# buff_statue.net
KiCad netlist of a schematic drawn in EAGLE
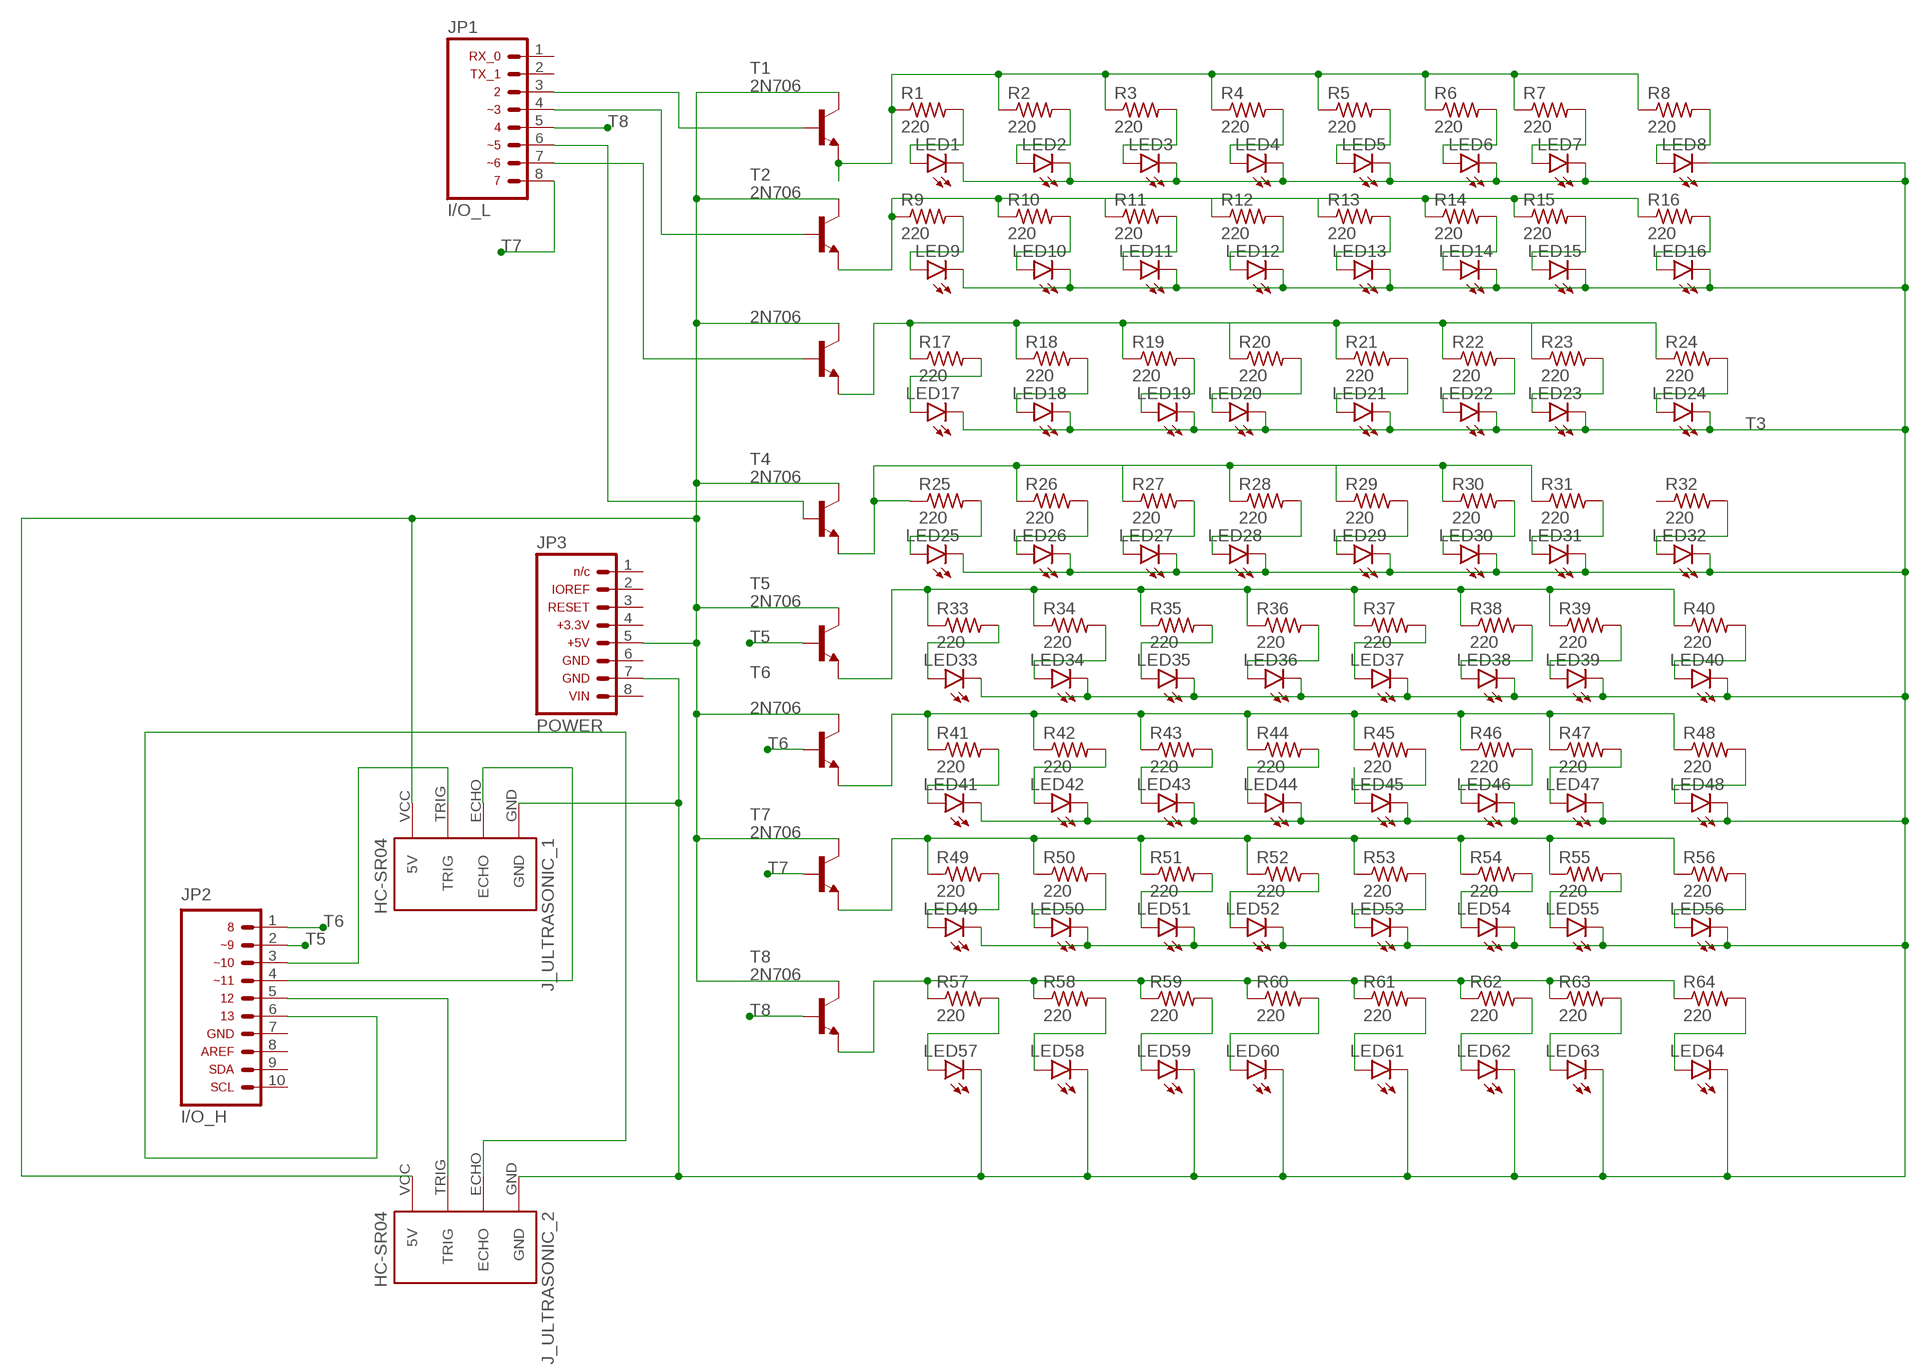
[diagram p0: schematic, sheet 1]

(export (version "E")
  (design (tool "Eeschema 10.0.6"))
  (components
    (comp (ref "JP1")
      (value "ARDUINO_CONN-IO_LSIP")
      (footprint "eagle-import:CONN-1X08")
      (libsource (lib "eagle-import") (part "ARDUINO_CONN-IO_LSIP"))
    )
    (comp (ref "JP2")
      (value "ARDUINO_CONN-IO_HSIP")
      (footprint "eagle-import:CONN-1X10")
      (libsource (lib "eagle-import") (part "ARDUINO_CONN-IO_HSIP"))
    )
    (comp (ref "JP3")
      (value "ARDUINO_CONN-POWERSIP")
      (footprint "eagle-import:CONN-1X08")
      (libsource (lib "eagle-import") (part "ARDUINO_CONN-POWERSIP"))
    )
    (comp (ref "J_ULTRASONIC_1")
      (value "HC-SR04")
      (footprint "eagle-import:HC-SR04_FOOTPRINT")
      (libsource (lib "eagle-import") (part "HC-SR04"))
    )
    (comp (ref "J_ULTRASONIC_2")
      (value "HC-SR04")
      (footprint "eagle-import:HC-SR04_FOOTPRINT")
      (libsource (lib "eagle-import") (part "HC-SR04"))
    )
    (comp (ref "LED1")
      (value "LED5MM")
      (footprint "eagle-import:LED5MM")
      (libsource (lib "eagle-import") (part "LED5MM"))
    )
    (comp (ref "LED2")
      (value "LED5MM")
      (footprint "eagle-import:LED5MM")
      (libsource (lib "eagle-import") (part "LED5MM"))
    )
    (comp (ref "LED3")
      (value "LED5MM")
      (footprint "eagle-import:LED5MM")
      (libsource (lib "eagle-import") (part "LED5MM"))
    )
    (comp (ref "LED4")
      (value "LED5MM")
      (footprint "eagle-import:LED5MM")
      (libsource (lib "eagle-import") (part "LED5MM"))
    )
    (comp (ref "LED5")
      (value "LED5MM")
      (footprint "eagle-import:LED5MM")
      (libsource (lib "eagle-import") (part "LED5MM"))
    )
    (comp (ref "LED6")
      (value "LED5MM")
      (footprint "eagle-import:LED5MM")
      (libsource (lib "eagle-import") (part "LED5MM"))
    )
    (comp (ref "LED7")
      (value "LED5MM")
      (footprint "eagle-import:LED5MM")
      (libsource (lib "eagle-import") (part "LED5MM"))
    )
    (comp (ref "LED8")
      (value "LED5MM")
      (footprint "eagle-import:LED5MM")
      (libsource (lib "eagle-import") (part "LED5MM"))
    )
    (comp (ref "LED9")
      (value "LED5MM")
      (footprint "eagle-import:LED5MM")
      (libsource (lib "eagle-import") (part "LED5MM"))
    )
    (comp (ref "LED10")
      (value "LED5MM")
      (footprint "eagle-import:LED5MM")
      (libsource (lib "eagle-import") (part "LED5MM"))
    )
    (comp (ref "LED11")
      (value "LED5MM")
      (footprint "eagle-import:LED5MM")
      (libsource (lib "eagle-import") (part "LED5MM"))
    )
    (comp (ref "LED12")
      (value "LED5MM")
      (footprint "eagle-import:LED5MM")
      (libsource (lib "eagle-import") (part "LED5MM"))
    )
    (comp (ref "LED13")
      (value "LED5MM")
      (footprint "eagle-import:LED5MM")
      (libsource (lib "eagle-import") (part "LED5MM"))
    )
    (comp (ref "LED14")
      (value "LED5MM")
      (footprint "eagle-import:LED5MM")
      (libsource (lib "eagle-import") (part "LED5MM"))
    )
    (comp (ref "LED15")
      (value "LED5MM")
      (footprint "eagle-import:LED5MM")
      (libsource (lib "eagle-import") (part "LED5MM"))
    )
    (comp (ref "LED16")
      (value "LED5MM")
      (footprint "eagle-import:LED5MM")
      (libsource (lib "eagle-import") (part "LED5MM"))
    )
    (comp (ref "LED17")
      (value "LED5MM")
      (footprint "eagle-import:LED5MM")
      (libsource (lib "eagle-import") (part "LED5MM"))
    )
    (comp (ref "LED18")
      (value "LED5MM")
      (footprint "eagle-import:LED5MM")
      (libsource (lib "eagle-import") (part "LED5MM"))
    )
    (comp (ref "LED19")
      (value "LED5MM")
      (footprint "eagle-import:LED5MM")
      (libsource (lib "eagle-import") (part "LED5MM"))
    )
    (comp (ref "LED20")
      (value "LED5MM")
      (footprint "eagle-import:LED5MM")
      (libsource (lib "eagle-import") (part "LED5MM"))
    )
    (comp (ref "LED21")
      (value "LED5MM")
      (footprint "eagle-import:LED5MM")
      (libsource (lib "eagle-import") (part "LED5MM"))
    )
    (comp (ref "LED22")
      (value "LED5MM")
      (footprint "eagle-import:LED5MM")
      (libsource (lib "eagle-import") (part "LED5MM"))
    )
    (comp (ref "LED23")
      (value "LED5MM")
      (footprint "eagle-import:LED5MM")
      (libsource (lib "eagle-import") (part "LED5MM"))
    )
    (comp (ref "LED24")
      (value "LED5MM")
      (footprint "eagle-import:LED5MM")
      (libsource (lib "eagle-import") (part "LED5MM"))
    )
    (comp (ref "LED25")
      (value "LED5MM")
      (footprint "eagle-import:LED5MM")
      (libsource (lib "eagle-import") (part "LED5MM"))
    )
    (comp (ref "LED26")
      (value "LED5MM")
      (footprint "eagle-import:LED5MM")
      (libsource (lib "eagle-import") (part "LED5MM"))
    )
    (comp (ref "LED27")
      (value "LED5MM")
      (footprint "eagle-import:LED5MM")
      (libsource (lib "eagle-import") (part "LED5MM"))
    )
    (comp (ref "LED28")
      (value "LED5MM")
      (footprint "eagle-import:LED5MM")
      (libsource (lib "eagle-import") (part "LED5MM"))
    )
    (comp (ref "LED29")
      (value "LED5MM")
      (footprint "eagle-import:LED5MM")
      (libsource (lib "eagle-import") (part "LED5MM"))
    )
    (comp (ref "LED30")
      (value "LED5MM")
      (footprint "eagle-import:LED5MM")
      (libsource (lib "eagle-import") (part "LED5MM"))
    )
    (comp (ref "LED31")
      (value "LED5MM")
      (footprint "eagle-import:LED5MM")
      (libsource (lib "eagle-import") (part "LED5MM"))
    )
    (comp (ref "LED32")
      (value "LED5MM")
      (footprint "eagle-import:LED5MM")
      (libsource (lib "eagle-import") (part "LED5MM"))
    )
    (comp (ref "LED33")
      (value "LED5MM")
      (footprint "eagle-import:LED5MM")
      (libsource (lib "eagle-import") (part "LED5MM"))
    )
    (comp (ref "LED34")
      (value "LED5MM")
      (footprint "eagle-import:LED5MM")
      (libsource (lib "eagle-import") (part "LED5MM"))
    )
    (comp (ref "LED35")
      (value "LED5MM")
      (footprint "eagle-import:LED5MM")
      (libsource (lib "eagle-import") (part "LED5MM"))
    )
    (comp (ref "LED36")
      (value "LED5MM")
      (footprint "eagle-import:LED5MM")
      (libsource (lib "eagle-import") (part "LED5MM"))
    )
    (comp (ref "LED37")
      (value "LED5MM")
      (footprint "eagle-import:LED5MM")
      (libsource (lib "eagle-import") (part "LED5MM"))
    )
    (comp (ref "LED38")
      (value "LED5MM")
      (footprint "eagle-import:LED5MM")
      (libsource (lib "eagle-import") (part "LED5MM"))
    )
    (comp (ref "LED39")
      (value "LED5MM")
      (footprint "eagle-import:LED5MM")
      (libsource (lib "eagle-import") (part "LED5MM"))
    )
    (comp (ref "LED40")
      (value "LED5MM")
      (footprint "eagle-import:LED5MM")
      (libsource (lib "eagle-import") (part "LED5MM"))
    )
    (comp (ref "LED41")
      (value "LED5MM")
      (footprint "eagle-import:LED5MM")
      (libsource (lib "eagle-import") (part "LED5MM"))
    )
    (comp (ref "LED42")
      (value "LED5MM")
      (footprint "eagle-import:LED5MM")
      (libsource (lib "eagle-import") (part "LED5MM"))
    )
    (comp (ref "LED43")
      (value "LED5MM")
      (footprint "eagle-import:LED5MM")
      (libsource (lib "eagle-import") (part "LED5MM"))
    )
    (comp (ref "LED44")
      (value "LED5MM")
      (footprint "eagle-import:LED5MM")
      (libsource (lib "eagle-import") (part "LED5MM"))
    )
    (comp (ref "LED45")
      (value "LED5MM")
      (footprint "eagle-import:LED5MM")
      (libsource (lib "eagle-import") (part "LED5MM"))
    )
    (comp (ref "LED46")
      (value "LED5MM")
      (footprint "eagle-import:LED5MM")
      (libsource (lib "eagle-import") (part "LED5MM"))
    )
    (comp (ref "LED47")
      (value "LED5MM")
      (footprint "eagle-import:LED5MM")
      (libsource (lib "eagle-import") (part "LED5MM"))
    )
    (comp (ref "LED48")
      (value "LED5MM")
      (footprint "eagle-import:LED5MM")
      (libsource (lib "eagle-import") (part "LED5MM"))
    )
    (comp (ref "LED49")
      (value "LED5MM")
      (footprint "eagle-import:LED5MM")
      (libsource (lib "eagle-import") (part "LED5MM"))
    )
    (comp (ref "LED50")
      (value "LED5MM")
      (footprint "eagle-import:LED5MM")
      (libsource (lib "eagle-import") (part "LED5MM"))
    )
    (comp (ref "LED51")
      (value "LED5MM")
      (footprint "eagle-import:LED5MM")
      (libsource (lib "eagle-import") (part "LED5MM"))
    )
    (comp (ref "LED52")
      (value "LED5MM")
      (footprint "eagle-import:LED5MM")
      (libsource (lib "eagle-import") (part "LED5MM"))
    )
    (comp (ref "LED53")
      (value "LED5MM")
      (footprint "eagle-import:LED5MM")
      (libsource (lib "eagle-import") (part "LED5MM"))
    )
    (comp (ref "LED54")
      (value "LED5MM")
      (footprint "eagle-import:LED5MM")
      (libsource (lib "eagle-import") (part "LED5MM"))
    )
    (comp (ref "LED55")
      (value "LED5MM")
      (footprint "eagle-import:LED5MM")
      (libsource (lib "eagle-import") (part "LED5MM"))
    )
    (comp (ref "LED56")
      (value "LED5MM")
      (footprint "eagle-import:LED5MM")
      (libsource (lib "eagle-import") (part "LED5MM"))
    )
    (comp (ref "LED57")
      (value "LED5MM")
      (footprint "eagle-import:LED5MM")
      (libsource (lib "eagle-import") (part "LED5MM"))
    )
    (comp (ref "LED58")
      (value "LED5MM")
      (footprint "eagle-import:LED5MM")
      (libsource (lib "eagle-import") (part "LED5MM"))
    )
    (comp (ref "LED59")
      (value "LED5MM")
      (footprint "eagle-import:LED5MM")
      (libsource (lib "eagle-import") (part "LED5MM"))
    )
    (comp (ref "LED60")
      (value "LED5MM")
      (footprint "eagle-import:LED5MM")
      (libsource (lib "eagle-import") (part "LED5MM"))
    )
    (comp (ref "LED61")
      (value "LED5MM")
      (footprint "eagle-import:LED5MM")
      (libsource (lib "eagle-import") (part "LED5MM"))
    )
    (comp (ref "LED62")
      (value "LED5MM")
      (footprint "eagle-import:LED5MM")
      (libsource (lib "eagle-import") (part "LED5MM"))
    )
    (comp (ref "LED63")
      (value "LED5MM")
      (footprint "eagle-import:LED5MM")
      (libsource (lib "eagle-import") (part "LED5MM"))
    )
    (comp (ref "LED64")
      (value "LED5MM")
      (footprint "eagle-import:LED5MM")
      (libsource (lib "eagle-import") (part "LED5MM"))
    )
    (comp (ref "R1")
      (value "220")
      (footprint "eagle-import:0204_7")
      (libsource (lib "eagle-import") (part "R-US_0204/7"))
    )
    (comp (ref "R2")
      (value "220")
      (footprint "eagle-import:0204_7")
      (libsource (lib "eagle-import") (part "R-US_0204/7"))
    )
    (comp (ref "R3")
      (value "220")
      (footprint "eagle-import:0204_7")
      (libsource (lib "eagle-import") (part "R-US_0204/7"))
    )
    (comp (ref "R4")
      (value "220")
      (footprint "eagle-import:0204_7")
      (libsource (lib "eagle-import") (part "R-US_0204/7"))
    )
    (comp (ref "R5")
      (value "220")
      (footprint "eagle-import:0204_7")
      (libsource (lib "eagle-import") (part "R-US_0204/7"))
    )
    (comp (ref "R6")
      (value "220")
      (footprint "eagle-import:0204_7")
      (libsource (lib "eagle-import") (part "R-US_0204/7"))
    )
    (comp (ref "R7")
      (value "220")
      (footprint "eagle-import:0204_7")
      (libsource (lib "eagle-import") (part "R-US_0204/7"))
    )
    (comp (ref "R8")
      (value "220")
      (footprint "eagle-import:0204_7")
      (libsource (lib "eagle-import") (part "R-US_0204/7"))
    )
    (comp (ref "R9")
      (value "220")
      (footprint "eagle-import:0204_7")
      (libsource (lib "eagle-import") (part "R-US_0204/7"))
    )
    (comp (ref "R10")
      (value "220")
      (footprint "eagle-import:0204_7")
      (libsource (lib "eagle-import") (part "R-US_0204/7"))
    )
    (comp (ref "R11")
      (value "220")
      (footprint "eagle-import:0204_7")
      (libsource (lib "eagle-import") (part "R-US_0204/7"))
    )
    (comp (ref "R12")
      (value "220")
      (footprint "eagle-import:0204_7")
      (libsource (lib "eagle-import") (part "R-US_0204/7"))
    )
    (comp (ref "R13")
      (value "220")
      (footprint "eagle-import:0204_7")
      (libsource (lib "eagle-import") (part "R-US_0204/7"))
    )
    (comp (ref "R14")
      (value "220")
      (footprint "eagle-import:0204_7")
      (libsource (lib "eagle-import") (part "R-US_0204/7"))
    )
    (comp (ref "R15")
      (value "220")
      (footprint "eagle-import:0204_7")
      (libsource (lib "eagle-import") (part "R-US_0204/7"))
    )
    (comp (ref "R16")
      (value "220")
      (footprint "eagle-import:0204_7")
      (libsource (lib "eagle-import") (part "R-US_0204/7"))
    )
    (comp (ref "R17")
      (value "220")
      (footprint "eagle-import:0204_7")
      (libsource (lib "eagle-import") (part "R-US_0204/7"))
    )
    (comp (ref "R18")
      (value "220")
      (footprint "eagle-import:0204_7")
      (libsource (lib "eagle-import") (part "R-US_0204/7"))
    )
    (comp (ref "R19")
      (value "220")
      (footprint "eagle-import:0204_7")
      (libsource (lib "eagle-import") (part "R-US_0204/7"))
    )
    (comp (ref "R20")
      (value "220")
      (footprint "eagle-import:0204_7")
      (libsource (lib "eagle-import") (part "R-US_0204/7"))
    )
    (comp (ref "R21")
      (value "220")
      (footprint "eagle-import:0204_7")
      (libsource (lib "eagle-import") (part "R-US_0204/7"))
    )
    (comp (ref "R22")
      (value "220")
      (footprint "eagle-import:0204_7")
      (libsource (lib "eagle-import") (part "R-US_0204/7"))
    )
    (comp (ref "R23")
      (value "220")
      (footprint "eagle-import:0204_7")
      (libsource (lib "eagle-import") (part "R-US_0204/7"))
    )
    (comp (ref "R24")
      (value "220")
      (footprint "eagle-import:0204_7")
      (libsource (lib "eagle-import") (part "R-US_0204/7"))
    )
    (comp (ref "R25")
      (value "220")
      (footprint "eagle-import:0204_7")
      (libsource (lib "eagle-import") (part "R-US_0204/7"))
    )
    (comp (ref "R26")
      (value "220")
      (footprint "eagle-import:0204_7")
      (libsource (lib "eagle-import") (part "R-US_0204/7"))
    )
    (comp (ref "R27")
      (value "220")
      (footprint "eagle-import:0204_7")
      (libsource (lib "eagle-import") (part "R-US_0204/7"))
    )
    (comp (ref "R28")
      (value "220")
      (footprint "eagle-import:0204_7")
      (libsource (lib "eagle-import") (part "R-US_0204/7"))
    )
    (comp (ref "R29")
      (value "220")
      (footprint "eagle-import:0204_7")
      (libsource (lib "eagle-import") (part "R-US_0204/7"))
    )
    (comp (ref "R30")
      (value "220")
      (footprint "eagle-import:0204_7")
      (libsource (lib "eagle-import") (part "R-US_0204/7"))
    )
    (comp (ref "R31")
      (value "220")
      (footprint "eagle-import:0204_7")
      (libsource (lib "eagle-import") (part "R-US_0204/7"))
    )
    (comp (ref "R32")
      (value "220")
      (footprint "eagle-import:0204_7")
      (libsource (lib "eagle-import") (part "R-US_0204/7"))
    )
    (comp (ref "R33")
      (value "220")
      (footprint "eagle-import:0204_7")
      (libsource (lib "eagle-import") (part "R-US_0204/7"))
    )
    (comp (ref "R34")
      (value "220")
      (footprint "eagle-import:0204_7")
      (libsource (lib "eagle-import") (part "R-US_0204/7"))
    )
    (comp (ref "R35")
      (value "220")
      (footprint "eagle-import:0204_7")
      (libsource (lib "eagle-import") (part "R-US_0204/7"))
    )
    (comp (ref "R36")
      (value "220")
      (footprint "eagle-import:0204_7")
      (libsource (lib "eagle-import") (part "R-US_0204/7"))
    )
    (comp (ref "R37")
      (value "220")
      (footprint "eagle-import:0204_7")
      (libsource (lib "eagle-import") (part "R-US_0204/7"))
    )
    (comp (ref "R38")
      (value "220")
      (footprint "eagle-import:0204_7")
      (libsource (lib "eagle-import") (part "R-US_0204/7"))
    )
    (comp (ref "R39")
      (value "220")
      (footprint "eagle-import:0204_7")
      (libsource (lib "eagle-import") (part "R-US_0204/7"))
    )
    (comp (ref "R40")
      (value "220")
      (footprint "eagle-import:0204_7")
      (libsource (lib "eagle-import") (part "R-US_0204/7"))
    )
    (comp (ref "R41")
      (value "220")
      (footprint "eagle-import:0204_7")
      (libsource (lib "eagle-import") (part "R-US_0204/7"))
    )
    (comp (ref "R42")
      (value "220")
      (footprint "eagle-import:0204_7")
      (libsource (lib "eagle-import") (part "R-US_0204/7"))
    )
    (comp (ref "R43")
      (value "220")
      (footprint "eagle-import:0204_7")
      (libsource (lib "eagle-import") (part "R-US_0204/7"))
    )
    (comp (ref "R44")
      (value "220")
      (footprint "eagle-import:0204_7")
      (libsource (lib "eagle-import") (part "R-US_0204/7"))
    )
    (comp (ref "R45")
      (value "220")
      (footprint "eagle-import:0204_7")
      (libsource (lib "eagle-import") (part "R-US_0204/7"))
    )
    (comp (ref "R46")
      (value "220")
      (footprint "eagle-import:0204_7")
      (libsource (lib "eagle-import") (part "R-US_0204/7"))
    )
    (comp (ref "R47")
      (value "220")
      (footprint "eagle-import:0204_7")
      (libsource (lib "eagle-import") (part "R-US_0204/7"))
    )
    (comp (ref "R48")
      (value "220")
      (footprint "eagle-import:0204_7")
      (libsource (lib "eagle-import") (part "R-US_0204/7"))
    )
    (comp (ref "R49")
      (value "220")
      (footprint "eagle-import:0204_7")
      (libsource (lib "eagle-import") (part "R-US_0204/7"))
    )
    (comp (ref "R50")
      (value "220")
      (footprint "eagle-import:0204_7")
      (libsource (lib "eagle-import") (part "R-US_0204/7"))
    )
    (comp (ref "R51")
      (value "220")
      (footprint "eagle-import:0204_7")
      (libsource (lib "eagle-import") (part "R-US_0204/7"))
    )
    (comp (ref "R52")
      (value "220")
      (footprint "eagle-import:0204_7")
      (libsource (lib "eagle-import") (part "R-US_0204/7"))
    )
    (comp (ref "R53")
      (value "220")
      (footprint "eagle-import:0204_7")
      (libsource (lib "eagle-import") (part "R-US_0204/7"))
    )
    (comp (ref "R54")
      (value "220")
      (footprint "eagle-import:0204_7")
      (libsource (lib "eagle-import") (part "R-US_0204/7"))
    )
    (comp (ref "R55")
      (value "220")
      (footprint "eagle-import:0204_7")
      (libsource (lib "eagle-import") (part "R-US_0204/7"))
    )
    (comp (ref "R56")
      (value "220")
      (footprint "eagle-import:0204_7")
      (libsource (lib "eagle-import") (part "R-US_0204/7"))
    )
    (comp (ref "R57")
      (value "220")
      (footprint "eagle-import:0204_7")
      (libsource (lib "eagle-import") (part "R-US_0204/7"))
    )
    (comp (ref "R58")
      (value "220")
      (footprint "eagle-import:0204_7")
      (libsource (lib "eagle-import") (part "R-US_0204/7"))
    )
    (comp (ref "R59")
      (value "220")
      (footprint "eagle-import:0204_7")
      (libsource (lib "eagle-import") (part "R-US_0204/7"))
    )
    (comp (ref "R60")
      (value "220")
      (footprint "eagle-import:0204_7")
      (libsource (lib "eagle-import") (part "R-US_0204/7"))
    )
    (comp (ref "R61")
      (value "220")
      (footprint "eagle-import:0204_7")
      (libsource (lib "eagle-import") (part "R-US_0204/7"))
    )
    (comp (ref "R62")
      (value "220")
      (footprint "eagle-import:0204_7")
      (libsource (lib "eagle-import") (part "R-US_0204/7"))
    )
    (comp (ref "R63")
      (value "220")
      (footprint "eagle-import:0204_7")
      (libsource (lib "eagle-import") (part "R-US_0204/7"))
    )
    (comp (ref "R64")
      (value "220")
      (footprint "eagle-import:0204_7")
      (libsource (lib "eagle-import") (part "R-US_0204/7"))
    )
    (comp (ref "T1")
      (value "2N706")
      (footprint "eagle-import:TO18")
      (libsource (lib "eagle-import") (part "2N706"))
    )
    (comp (ref "T2")
      (value "2N706")
      (footprint "eagle-import:TO18")
      (libsource (lib "eagle-import") (part "2N706"))
    )
    (comp (ref "T3")
      (value "2N706")
      (footprint "eagle-import:TO18")
      (libsource (lib "eagle-import") (part "2N706"))
    )
    (comp (ref "T4")
      (value "2N706")
      (footprint "eagle-import:TO18")
      (libsource (lib "eagle-import") (part "2N706"))
    )
    (comp (ref "T5")
      (value "2N706")
      (footprint "eagle-import:TO18")
      (libsource (lib "eagle-import") (part "2N706"))
    )
    (comp (ref "T6")
      (value "2N706")
      (footprint "eagle-import:TO18")
      (libsource (lib "eagle-import") (part "2N706"))
    )
    (comp (ref "T7")
      (value "2N706")
      (footprint "eagle-import:TO18")
      (libsource (lib "eagle-import") (part "2N706"))
    )
    (comp (ref "T8")
      (value "2N706")
      (footprint "eagle-import:TO18")
      (libsource (lib "eagle-import") (part "2N706"))
    )
  )
  (nets
    (net (code "1") (name "/T5") (class "Default")
      (node (ref "JP2") (pin "2") (pinfunction "2_2") (pintype "passive"))
      (node (ref "T5") (pin "2") (pinfunction "B_2") (pintype "passive"))
    )
    (net (code "2") (name "/T6") (class "Default")
      (node (ref "JP2") (pin "1") (pinfunction "1_1") (pintype "passive"))
      (node (ref "T6") (pin "2") (pinfunction "B_2") (pintype "passive"))
    )
    (net (code "3") (name "/T7") (class "Default")
      (node (ref "JP1") (pin "8") (pinfunction "8_8") (pintype "passive"))
      (node (ref "T7") (pin "2") (pinfunction "B_2") (pintype "passive"))
    )
    (net (code "4") (name "/T8") (class "Default")
      (node (ref "JP1") (pin "5") (pinfunction "5_5") (pintype "passive"))
      (node (ref "T8") (pin "2") (pinfunction "B_2") (pintype "passive"))
    )
    (net (code "5") (name "Net-(JP2-Pad3)") (class "Default")
      (node (ref "JP2") (pin "3") (pinfunction "3_3") (pintype "passive"))
      (node (ref "J_ULTRASONIC_1") (pin "TRIG") (pinfunction "TRIG_TRIG") (pintype "bidirectional"))
    )
    (net (code "6") (name "Net-(JP2-Pad4)") (class "Default")
      (node (ref "JP2") (pin "4") (pinfunction "4_4") (pintype "passive"))
      (node (ref "J_ULTRASONIC_1") (pin "ECHO") (pinfunction "ECHO_ECHO") (pintype "bidirectional"))
    )
    (net (code "7") (name "Net-(JP2-Pad5)") (class "Default")
      (node (ref "JP2") (pin "5") (pinfunction "5_5") (pintype "passive"))
      (node (ref "J_ULTRASONIC_2") (pin "TRIG") (pinfunction "TRIG_TRIG") (pintype "bidirectional"))
    )
    (net (code "8") (name "Net-(JP2-Pad6)") (class "Default")
      (node (ref "JP2") (pin "6") (pinfunction "6_6") (pintype "passive"))
      (node (ref "J_ULTRASONIC_2") (pin "ECHO") (pinfunction "ECHO_ECHO") (pintype "bidirectional"))
    )
    (net (code "9") (name "Net-(J_ULTRASONIC_1-5V)") (class "Default")
      (node (ref "JP3") (pin "5") (pinfunction "5_5") (pintype "passive"))
      (node (ref "J_ULTRASONIC_1") (pin "VCC") (pinfunction "5V_VCC") (pintype "bidirectional"))
      (node (ref "J_ULTRASONIC_2") (pin "VCC") (pinfunction "5V_VCC") (pintype "bidirectional"))
      (node (ref "T1") (pin "3") (pinfunction "C_3") (pintype "passive"))
      (node (ref "T2") (pin "3") (pinfunction "C_3") (pintype "passive"))
      (node (ref "T3") (pin "3") (pinfunction "C_3") (pintype "passive"))
      (node (ref "T4") (pin "3") (pinfunction "C_3") (pintype "passive"))
      (node (ref "T5") (pin "3") (pinfunction "C_3") (pintype "passive"))
      (node (ref "T6") (pin "3") (pinfunction "C_3") (pintype "passive"))
      (node (ref "T7") (pin "3") (pinfunction "C_3") (pintype "passive"))
      (node (ref "T8") (pin "3") (pinfunction "C_3") (pintype "passive"))
    )
    (net (code "10") (name "Net-(LED1-C)") (class "Default")
      (node (ref "JP3") (pin "7") (pinfunction "7_7") (pintype "passive"))
      (node (ref "J_ULTRASONIC_1") (pin "GND") (pinfunction "GND_GND") (pintype "bidirectional"))
      (node (ref "J_ULTRASONIC_2") (pin "GND") (pinfunction "GND_GND") (pintype "bidirectional"))
      (node (ref "LED1") (pin "K") (pinfunction "C_K") (pintype "passive"))
      (node (ref "LED10") (pin "K") (pinfunction "C_K") (pintype "passive"))
      (node (ref "LED11") (pin "K") (pinfunction "C_K") (pintype "passive"))
      (node (ref "LED12") (pin "K") (pinfunction "C_K") (pintype "passive"))
      (node (ref "LED13") (pin "K") (pinfunction "C_K") (pintype "passive"))
      (node (ref "LED14") (pin "K") (pinfunction "C_K") (pintype "passive"))
      (node (ref "LED15") (pin "K") (pinfunction "C_K") (pintype "passive"))
      (node (ref "LED16") (pin "K") (pinfunction "C_K") (pintype "passive"))
      (node (ref "LED17") (pin "K") (pinfunction "C_K") (pintype "passive"))
      (node (ref "LED18") (pin "K") (pinfunction "C_K") (pintype "passive"))
      (node (ref "LED19") (pin "K") (pinfunction "C_K") (pintype "passive"))
      (node (ref "LED2") (pin "K") (pinfunction "C_K") (pintype "passive"))
      (node (ref "LED20") (pin "K") (pinfunction "C_K") (pintype "passive"))
      (node (ref "LED21") (pin "K") (pinfunction "C_K") (pintype "passive"))
      (node (ref "LED22") (pin "K") (pinfunction "C_K") (pintype "passive"))
      (node (ref "LED23") (pin "K") (pinfunction "C_K") (pintype "passive"))
      (node (ref "LED24") (pin "K") (pinfunction "C_K") (pintype "passive"))
      (node (ref "LED25") (pin "K") (pinfunction "C_K") (pintype "passive"))
      (node (ref "LED26") (pin "K") (pinfunction "C_K") (pintype "passive"))
      (node (ref "LED27") (pin "K") (pinfunction "C_K") (pintype "passive"))
      (node (ref "LED28") (pin "K") (pinfunction "C_K") (pintype "passive"))
      (node (ref "LED29") (pin "K") (pinfunction "C_K") (pintype "passive"))
      (node (ref "LED3") (pin "K") (pinfunction "C_K") (pintype "passive"))
      (node (ref "LED30") (pin "K") (pinfunction "C_K") (pintype "passive"))
      (node (ref "LED31") (pin "K") (pinfunction "C_K") (pintype "passive"))
      (node (ref "LED32") (pin "K") (pinfunction "C_K") (pintype "passive"))
      (node (ref "LED33") (pin "K") (pinfunction "C_K") (pintype "passive"))
      (node (ref "LED34") (pin "K") (pinfunction "C_K") (pintype "passive"))
      (node (ref "LED35") (pin "K") (pinfunction "C_K") (pintype "passive"))
      (node (ref "LED36") (pin "K") (pinfunction "C_K") (pintype "passive"))
      (node (ref "LED37") (pin "K") (pinfunction "C_K") (pintype "passive"))
      (node (ref "LED38") (pin "K") (pinfunction "C_K") (pintype "passive"))
      (node (ref "LED39") (pin "K") (pinfunction "C_K") (pintype "passive"))
      (node (ref "LED4") (pin "K") (pinfunction "C_K") (pintype "passive"))
      (node (ref "LED40") (pin "K") (pinfunction "C_K") (pintype "passive"))
      (node (ref "LED41") (pin "K") (pinfunction "C_K") (pintype "passive"))
      (node (ref "LED42") (pin "K") (pinfunction "C_K") (pintype "passive"))
      (node (ref "LED43") (pin "K") (pinfunction "C_K") (pintype "passive"))
      (node (ref "LED44") (pin "K") (pinfunction "C_K") (pintype "passive"))
      (node (ref "LED45") (pin "K") (pinfunction "C_K") (pintype "passive"))
      (node (ref "LED46") (pin "K") (pinfunction "C_K") (pintype "passive"))
      (node (ref "LED47") (pin "K") (pinfunction "C_K") (pintype "passive"))
      (node (ref "LED48") (pin "K") (pinfunction "C_K") (pintype "passive"))
      (node (ref "LED49") (pin "K") (pinfunction "C_K") (pintype "passive"))
      (node (ref "LED5") (pin "K") (pinfunction "C_K") (pintype "passive"))
      (node (ref "LED50") (pin "K") (pinfunction "C_K") (pintype "passive"))
      (node (ref "LED51") (pin "K") (pinfunction "C_K") (pintype "passive"))
      (node (ref "LED52") (pin "K") (pinfunction "C_K") (pintype "passive"))
      (node (ref "LED53") (pin "K") (pinfunction "C_K") (pintype "passive"))
      (node (ref "LED54") (pin "K") (pinfunction "C_K") (pintype "passive"))
      (node (ref "LED55") (pin "K") (pinfunction "C_K") (pintype "passive"))
      (node (ref "LED56") (pin "K") (pinfunction "C_K") (pintype "passive"))
      (node (ref "LED57") (pin "K") (pinfunction "C_K") (pintype "passive"))
      (node (ref "LED58") (pin "K") (pinfunction "C_K") (pintype "passive"))
      (node (ref "LED59") (pin "K") (pinfunction "C_K") (pintype "passive"))
      (node (ref "LED6") (pin "K") (pinfunction "C_K") (pintype "passive"))
      (node (ref "LED60") (pin "K") (pinfunction "C_K") (pintype "passive"))
      (node (ref "LED61") (pin "K") (pinfunction "C_K") (pintype "passive"))
      (node (ref "LED62") (pin "K") (pinfunction "C_K") (pintype "passive"))
      (node (ref "LED63") (pin "K") (pinfunction "C_K") (pintype "passive"))
      (node (ref "LED64") (pin "K") (pinfunction "C_K") (pintype "passive"))
      (node (ref "LED7") (pin "K") (pinfunction "C_K") (pintype "passive"))
      (node (ref "LED8") (pin "K") (pinfunction "C_K") (pintype "passive"))
      (node (ref "LED9") (pin "K") (pinfunction "C_K") (pintype "passive"))
    )
    (net (code "11") (name "Net-(LED1-PadA)") (class "Default")
      (node (ref "LED1") (pin "A") (pinfunction "A_A") (pintype "passive"))
      (node (ref "R1") (pin "2") (pinfunction "2_2") (pintype "passive"))
    )
    (net (code "12") (name "Net-(LED2-PadA)") (class "Default")
      (node (ref "LED2") (pin "A") (pinfunction "A_A") (pintype "passive"))
      (node (ref "R2") (pin "2") (pinfunction "2_2") (pintype "passive"))
    )
    (net (code "13") (name "Net-(LED3-PadA)") (class "Default")
      (node (ref "LED3") (pin "A") (pinfunction "A_A") (pintype "passive"))
      (node (ref "R3") (pin "2") (pinfunction "2_2") (pintype "passive"))
    )
    (net (code "14") (name "Net-(LED4-PadA)") (class "Default")
      (node (ref "LED4") (pin "A") (pinfunction "A_A") (pintype "passive"))
      (node (ref "R4") (pin "2") (pinfunction "2_2") (pintype "passive"))
    )
    (net (code "15") (name "Net-(LED5-PadA)") (class "Default")
      (node (ref "LED5") (pin "A") (pinfunction "A_A") (pintype "passive"))
      (node (ref "R5") (pin "2") (pinfunction "2_2") (pintype "passive"))
    )
    (net (code "16") (name "Net-(LED6-PadA)") (class "Default")
      (node (ref "LED6") (pin "A") (pinfunction "A_A") (pintype "passive"))
      (node (ref "R6") (pin "2") (pinfunction "2_2") (pintype "passive"))
    )
    (net (code "17") (name "Net-(LED7-PadA)") (class "Default")
      (node (ref "LED7") (pin "A") (pinfunction "A_A") (pintype "passive"))
      (node (ref "R7") (pin "2") (pinfunction "2_2") (pintype "passive"))
    )
    (net (code "18") (name "Net-(LED8-PadA)") (class "Default")
      (node (ref "LED8") (pin "A") (pinfunction "A_A") (pintype "passive"))
      (node (ref "R8") (pin "2") (pinfunction "2_2") (pintype "passive"))
    )
    (net (code "19") (name "Net-(LED9-PadA)") (class "Default")
      (node (ref "LED9") (pin "A") (pinfunction "A_A") (pintype "passive"))
      (node (ref "R9") (pin "2") (pinfunction "2_2") (pintype "passive"))
    )
    (net (code "20") (name "Net-(LED10-PadA)") (class "Default")
      (node (ref "LED10") (pin "A") (pinfunction "A_A") (pintype "passive"))
      (node (ref "R10") (pin "2") (pinfunction "2_2") (pintype "passive"))
    )
    (net (code "21") (name "Net-(LED11-PadA)") (class "Default")
      (node (ref "LED11") (pin "A") (pinfunction "A_A") (pintype "passive"))
      (node (ref "R11") (pin "2") (pinfunction "2_2") (pintype "passive"))
    )
    (net (code "22") (name "Net-(LED12-PadA)") (class "Default")
      (node (ref "LED12") (pin "A") (pinfunction "A_A") (pintype "passive"))
      (node (ref "R12") (pin "2") (pinfunction "2_2") (pintype "passive"))
    )
    (net (code "23") (name "Net-(LED13-PadA)") (class "Default")
      (node (ref "LED13") (pin "A") (pinfunction "A_A") (pintype "passive"))
      (node (ref "R13") (pin "2") (pinfunction "2_2") (pintype "passive"))
    )
    (net (code "24") (name "Net-(LED14-PadA)") (class "Default")
      (node (ref "LED14") (pin "A") (pinfunction "A_A") (pintype "passive"))
      (node (ref "R14") (pin "2") (pinfunction "2_2") (pintype "passive"))
    )
    (net (code "25") (name "Net-(LED15-PadA)") (class "Default")
      (node (ref "LED15") (pin "A") (pinfunction "A_A") (pintype "passive"))
      (node (ref "R15") (pin "2") (pinfunction "2_2") (pintype "passive"))
    )
    (net (code "26") (name "Net-(LED16-PadA)") (class "Default")
      (node (ref "LED16") (pin "A") (pinfunction "A_A") (pintype "passive"))
      (node (ref "R16") (pin "2") (pinfunction "2_2") (pintype "passive"))
    )
    (net (code "27") (name "Net-(LED17-PadA)") (class "Default")
      (node (ref "LED17") (pin "A") (pinfunction "A_A") (pintype "passive"))
      (node (ref "R17") (pin "2") (pinfunction "2_2") (pintype "passive"))
    )
    (net (code "28") (name "Net-(LED18-PadA)") (class "Default")
      (node (ref "LED18") (pin "A") (pinfunction "A_A") (pintype "passive"))
      (node (ref "R18") (pin "2") (pinfunction "2_2") (pintype "passive"))
    )
    (net (code "29") (name "Net-(LED19-PadA)") (class "Default")
      (node (ref "LED19") (pin "A") (pinfunction "A_A") (pintype "passive"))
      (node (ref "R19") (pin "2") (pinfunction "2_2") (pintype "passive"))
    )
    (net (code "30") (name "Net-(LED20-PadA)") (class "Default")
      (node (ref "LED20") (pin "A") (pinfunction "A_A") (pintype "passive"))
      (node (ref "R20") (pin "2") (pinfunction "2_2") (pintype "passive"))
    )
    (net (code "31") (name "Net-(LED21-PadA)") (class "Default")
      (node (ref "LED21") (pin "A") (pinfunction "A_A") (pintype "passive"))
      (node (ref "R21") (pin "2") (pinfunction "2_2") (pintype "passive"))
    )
    (net (code "32") (name "Net-(LED22-PadA)") (class "Default")
      (node (ref "LED22") (pin "A") (pinfunction "A_A") (pintype "passive"))
      (node (ref "R22") (pin "2") (pinfunction "2_2") (pintype "passive"))
    )
    (net (code "33") (name "Net-(LED23-PadA)") (class "Default")
      (node (ref "LED23") (pin "A") (pinfunction "A_A") (pintype "passive"))
      (node (ref "R23") (pin "2") (pinfunction "2_2") (pintype "passive"))
    )
    (net (code "34") (name "Net-(LED24-PadA)") (class "Default")
      (node (ref "LED24") (pin "A") (pinfunction "A_A") (pintype "passive"))
      (node (ref "R24") (pin "2") (pinfunction "2_2") (pintype "passive"))
    )
    (net (code "35") (name "Net-(LED25-PadA)") (class "Default")
      (node (ref "LED25") (pin "A") (pinfunction "A_A") (pintype "passive"))
      (node (ref "R25") (pin "2") (pinfunction "2_2") (pintype "passive"))
    )
    (net (code "36") (name "Net-(LED26-PadA)") (class "Default")
      (node (ref "LED26") (pin "A") (pinfunction "A_A") (pintype "passive"))
      (node (ref "R26") (pin "2") (pinfunction "2_2") (pintype "passive"))
    )
    (net (code "37") (name "Net-(LED27-PadA)") (class "Default")
      (node (ref "LED27") (pin "A") (pinfunction "A_A") (pintype "passive"))
      (node (ref "R27") (pin "2") (pinfunction "2_2") (pintype "passive"))
    )
    (net (code "38") (name "Net-(LED28-PadA)") (class "Default")
      (node (ref "LED28") (pin "A") (pinfunction "A_A") (pintype "passive"))
      (node (ref "R28") (pin "2") (pinfunction "2_2") (pintype "passive"))
    )
    (net (code "39") (name "Net-(LED29-PadA)") (class "Default")
      (node (ref "LED29") (pin "A") (pinfunction "A_A") (pintype "passive"))
      (node (ref "R29") (pin "2") (pinfunction "2_2") (pintype "passive"))
    )
    (net (code "40") (name "Net-(LED30-PadA)") (class "Default")
      (node (ref "LED30") (pin "A") (pinfunction "A_A") (pintype "passive"))
      (node (ref "R30") (pin "2") (pinfunction "2_2") (pintype "passive"))
    )
    (net (code "41") (name "Net-(LED31-PadA)") (class "Default")
      (node (ref "LED31") (pin "A") (pinfunction "A_A") (pintype "passive"))
      (node (ref "R31") (pin "2") (pinfunction "2_2") (pintype "passive"))
    )
    (net (code "42") (name "Net-(LED32-PadA)") (class "Default")
      (node (ref "LED32") (pin "A") (pinfunction "A_A") (pintype "passive"))
      (node (ref "R32") (pin "2") (pinfunction "2_2") (pintype "passive"))
    )
    (net (code "43") (name "Net-(LED33-PadA)") (class "Default")
      (node (ref "LED33") (pin "A") (pinfunction "A_A") (pintype "passive"))
      (node (ref "R33") (pin "2") (pinfunction "2_2") (pintype "passive"))
    )
    (net (code "44") (name "Net-(LED34-PadA)") (class "Default")
      (node (ref "LED34") (pin "A") (pinfunction "A_A") (pintype "passive"))
      (node (ref "R34") (pin "2") (pinfunction "2_2") (pintype "passive"))
    )
    (net (code "45") (name "Net-(LED35-PadA)") (class "Default")
      (node (ref "LED35") (pin "A") (pinfunction "A_A") (pintype "passive"))
      (node (ref "R35") (pin "2") (pinfunction "2_2") (pintype "passive"))
    )
    (net (code "46") (name "Net-(LED36-PadA)") (class "Default")
      (node (ref "LED36") (pin "A") (pinfunction "A_A") (pintype "passive"))
      (node (ref "R36") (pin "2") (pinfunction "2_2") (pintype "passive"))
    )
    (net (code "47") (name "Net-(LED37-PadA)") (class "Default")
      (node (ref "LED37") (pin "A") (pinfunction "A_A") (pintype "passive"))
      (node (ref "R37") (pin "2") (pinfunction "2_2") (pintype "passive"))
    )
    (net (code "48") (name "Net-(LED38-PadA)") (class "Default")
      (node (ref "LED38") (pin "A") (pinfunction "A_A") (pintype "passive"))
      (node (ref "R38") (pin "2") (pinfunction "2_2") (pintype "passive"))
    )
    (net (code "49") (name "Net-(LED39-PadA)") (class "Default")
      (node (ref "LED39") (pin "A") (pinfunction "A_A") (pintype "passive"))
      (node (ref "R39") (pin "2") (pinfunction "2_2") (pintype "passive"))
    )
    (net (code "50") (name "Net-(LED40-PadA)") (class "Default")
      (node (ref "LED40") (pin "A") (pinfunction "A_A") (pintype "passive"))
      (node (ref "R40") (pin "2") (pinfunction "2_2") (pintype "passive"))
    )
    (net (code "51") (name "Net-(LED41-PadA)") (class "Default")
      (node (ref "LED41") (pin "A") (pinfunction "A_A") (pintype "passive"))
      (node (ref "R41") (pin "2") (pinfunction "2_2") (pintype "passive"))
    )
    (net (code "52") (name "Net-(LED42-PadA)") (class "Default")
      (node (ref "LED42") (pin "A") (pinfunction "A_A") (pintype "passive"))
      (node (ref "R42") (pin "2") (pinfunction "2_2") (pintype "passive"))
    )
    (net (code "53") (name "Net-(LED43-PadA)") (class "Default")
      (node (ref "LED43") (pin "A") (pinfunction "A_A") (pintype "passive"))
      (node (ref "R43") (pin "2") (pinfunction "2_2") (pintype "passive"))
    )
    (net (code "54") (name "Net-(LED44-PadA)") (class "Default")
      (node (ref "LED44") (pin "A") (pinfunction "A_A") (pintype "passive"))
      (node (ref "R44") (pin "2") (pinfunction "2_2") (pintype "passive"))
    )
    (net (code "55") (name "Net-(LED45-PadA)") (class "Default")
      (node (ref "LED45") (pin "A") (pinfunction "A_A") (pintype "passive"))
      (node (ref "R45") (pin "2") (pinfunction "2_2") (pintype "passive"))
    )
    (net (code "56") (name "Net-(LED46-PadA)") (class "Default")
      (node (ref "LED46") (pin "A") (pinfunction "A_A") (pintype "passive"))
      (node (ref "R46") (pin "2") (pinfunction "2_2") (pintype "passive"))
    )
    (net (code "57") (name "Net-(LED47-PadA)") (class "Default")
      (node (ref "LED47") (pin "A") (pinfunction "A_A") (pintype "passive"))
      (node (ref "R47") (pin "2") (pinfunction "2_2") (pintype "passive"))
    )
    (net (code "58") (name "Net-(LED48-PadA)") (class "Default")
      (node (ref "LED48") (pin "A") (pinfunction "A_A") (pintype "passive"))
      (node (ref "R48") (pin "2") (pinfunction "2_2") (pintype "passive"))
    )
    (net (code "59") (name "Net-(LED49-PadA)") (class "Default")
      (node (ref "LED49") (pin "A") (pinfunction "A_A") (pintype "passive"))
      (node (ref "R49") (pin "2") (pinfunction "2_2") (pintype "passive"))
    )
    (net (code "60") (name "Net-(LED50-PadA)") (class "Default")
      (node (ref "LED50") (pin "A") (pinfunction "A_A") (pintype "passive"))
      (node (ref "R50") (pin "2") (pinfunction "2_2") (pintype "passive"))
    )
    (net (code "61") (name "Net-(LED51-PadA)") (class "Default")
      (node (ref "LED51") (pin "A") (pinfunction "A_A") (pintype "passive"))
      (node (ref "R51") (pin "2") (pinfunction "2_2") (pintype "passive"))
    )
    (net (code "62") (name "Net-(LED52-PadA)") (class "Default")
      (node (ref "LED52") (pin "A") (pinfunction "A_A") (pintype "passive"))
      (node (ref "R52") (pin "2") (pinfunction "2_2") (pintype "passive"))
    )
    (net (code "63") (name "Net-(LED53-PadA)") (class "Default")
      (node (ref "LED53") (pin "A") (pinfunction "A_A") (pintype "passive"))
      (node (ref "R53") (pin "2") (pinfunction "2_2") (pintype "passive"))
    )
    (net (code "64") (name "Net-(LED54-PadA)") (class "Default")
      (node (ref "LED54") (pin "A") (pinfunction "A_A") (pintype "passive"))
      (node (ref "R54") (pin "2") (pinfunction "2_2") (pintype "passive"))
    )
    (net (code "65") (name "Net-(LED55-PadA)") (class "Default")
      (node (ref "LED55") (pin "A") (pinfunction "A_A") (pintype "passive"))
      (node (ref "R55") (pin "2") (pinfunction "2_2") (pintype "passive"))
    )
    (net (code "66") (name "Net-(LED56-PadA)") (class "Default")
      (node (ref "LED56") (pin "A") (pinfunction "A_A") (pintype "passive"))
      (node (ref "R56") (pin "2") (pinfunction "2_2") (pintype "passive"))
    )
    (net (code "67") (name "Net-(LED57-PadA)") (class "Default")
      (node (ref "LED57") (pin "A") (pinfunction "A_A") (pintype "passive"))
      (node (ref "R57") (pin "2") (pinfunction "2_2") (pintype "passive"))
    )
    (net (code "68") (name "Net-(LED58-PadA)") (class "Default")
      (node (ref "LED58") (pin "A") (pinfunction "A_A") (pintype "passive"))
      (node (ref "R58") (pin "2") (pinfunction "2_2") (pintype "passive"))
    )
    (net (code "69") (name "Net-(LED59-PadA)") (class "Default")
      (node (ref "LED59") (pin "A") (pinfunction "A_A") (pintype "passive"))
      (node (ref "R59") (pin "2") (pinfunction "2_2") (pintype "passive"))
    )
    (net (code "70") (name "Net-(LED60-PadA)") (class "Default")
      (node (ref "LED60") (pin "A") (pinfunction "A_A") (pintype "passive"))
      (node (ref "R60") (pin "2") (pinfunction "2_2") (pintype "passive"))
    )
    (net (code "71") (name "Net-(LED61-PadA)") (class "Default")
      (node (ref "LED61") (pin "A") (pinfunction "A_A") (pintype "passive"))
      (node (ref "R61") (pin "2") (pinfunction "2_2") (pintype "passive"))
    )
    (net (code "72") (name "Net-(LED62-PadA)") (class "Default")
      (node (ref "LED62") (pin "A") (pinfunction "A_A") (pintype "passive"))
      (node (ref "R62") (pin "2") (pinfunction "2_2") (pintype "passive"))
    )
    (net (code "73") (name "Net-(LED63-PadA)") (class "Default")
      (node (ref "LED63") (pin "A") (pinfunction "A_A") (pintype "passive"))
      (node (ref "R63") (pin "2") (pinfunction "2_2") (pintype "passive"))
    )
    (net (code "74") (name "Net-(LED64-PadA)") (class "Default")
      (node (ref "LED64") (pin "A") (pinfunction "A_A") (pintype "passive"))
      (node (ref "R64") (pin "2") (pinfunction "2_2") (pintype "passive"))
    )
    (net (code "75") (name "Net-(T1-B)") (class "Default")
      (node (ref "JP1") (pin "3") (pinfunction "3_3") (pintype "passive"))
      (node (ref "T1") (pin "2") (pinfunction "B_2") (pintype "passive"))
    )
    (net (code "76") (name "Net-(T1-E)") (class "Default")
      (node (ref "R1") (pin "1") (pinfunction "1_1") (pintype "passive"))
      (node (ref "R2") (pin "1") (pinfunction "1_1") (pintype "passive"))
      (node (ref "R3") (pin "1") (pinfunction "1_1") (pintype "passive"))
      (node (ref "R4") (pin "1") (pinfunction "1_1") (pintype "passive"))
      (node (ref "R5") (pin "1") (pinfunction "1_1") (pintype "passive"))
      (node (ref "R6") (pin "1") (pinfunction "1_1") (pintype "passive"))
      (node (ref "R7") (pin "1") (pinfunction "1_1") (pintype "passive"))
      (node (ref "R8") (pin "1") (pinfunction "1_1") (pintype "passive"))
      (node (ref "T1") (pin "1") (pinfunction "E_1") (pintype "passive"))
    )
    (net (code "77") (name "Net-(T2-B)") (class "Default")
      (node (ref "JP1") (pin "4") (pinfunction "4_4") (pintype "passive"))
      (node (ref "T2") (pin "2") (pinfunction "B_2") (pintype "passive"))
    )
    (net (code "78") (name "Net-(T2-E)") (class "Default")
      (node (ref "R10") (pin "1") (pinfunction "1_1") (pintype "passive"))
      (node (ref "R11") (pin "1") (pinfunction "1_1") (pintype "passive"))
      (node (ref "R12") (pin "1") (pinfunction "1_1") (pintype "passive"))
      (node (ref "R13") (pin "1") (pinfunction "1_1") (pintype "passive"))
      (node (ref "R14") (pin "1") (pinfunction "1_1") (pintype "passive"))
      (node (ref "R15") (pin "1") (pinfunction "1_1") (pintype "passive"))
      (node (ref "R16") (pin "1") (pinfunction "1_1") (pintype "passive"))
      (node (ref "R9") (pin "1") (pinfunction "1_1") (pintype "passive"))
      (node (ref "T2") (pin "1") (pinfunction "E_1") (pintype "passive"))
    )
    (net (code "79") (name "Net-(T3-B)") (class "Default")
      (node (ref "JP1") (pin "7") (pinfunction "7_7") (pintype "passive"))
      (node (ref "T3") (pin "2") (pinfunction "B_2") (pintype "passive"))
    )
    (net (code "80") (name "Net-(T3-E)") (class "Default")
      (node (ref "R17") (pin "1") (pinfunction "1_1") (pintype "passive"))
      (node (ref "R18") (pin "1") (pinfunction "1_1") (pintype "passive"))
      (node (ref "R19") (pin "1") (pinfunction "1_1") (pintype "passive"))
      (node (ref "R20") (pin "1") (pinfunction "1_1") (pintype "passive"))
      (node (ref "R21") (pin "1") (pinfunction "1_1") (pintype "passive"))
      (node (ref "R22") (pin "1") (pinfunction "1_1") (pintype "passive"))
      (node (ref "R23") (pin "1") (pinfunction "1_1") (pintype "passive"))
      (node (ref "R24") (pin "1") (pinfunction "1_1") (pintype "passive"))
      (node (ref "T3") (pin "1") (pinfunction "E_1") (pintype "passive"))
    )
    (net (code "81") (name "Net-(T4-B)") (class "Default")
      (node (ref "JP1") (pin "6") (pinfunction "6_6") (pintype "passive"))
      (node (ref "T4") (pin "2") (pinfunction "B_2") (pintype "passive"))
    )
    (net (code "82") (name "Net-(T4-E)") (class "Default")
      (node (ref "R25") (pin "1") (pinfunction "1_1") (pintype "passive"))
      (node (ref "R26") (pin "1") (pinfunction "1_1") (pintype "passive"))
      (node (ref "R27") (pin "1") (pinfunction "1_1") (pintype "passive"))
      (node (ref "R28") (pin "1") (pinfunction "1_1") (pintype "passive"))
      (node (ref "R29") (pin "1") (pinfunction "1_1") (pintype "passive"))
      (node (ref "R30") (pin "1") (pinfunction "1_1") (pintype "passive"))
      (node (ref "R31") (pin "1") (pinfunction "1_1") (pintype "passive"))
      (node (ref "T4") (pin "1") (pinfunction "E_1") (pintype "passive"))
    )
    (net (code "83") (name "Net-(T5-E)") (class "Default")
      (node (ref "R33") (pin "1") (pinfunction "1_1") (pintype "passive"))
      (node (ref "R34") (pin "1") (pinfunction "1_1") (pintype "passive"))
      (node (ref "R35") (pin "1") (pinfunction "1_1") (pintype "passive"))
      (node (ref "R36") (pin "1") (pinfunction "1_1") (pintype "passive"))
      (node (ref "R37") (pin "1") (pinfunction "1_1") (pintype "passive"))
      (node (ref "R38") (pin "1") (pinfunction "1_1") (pintype "passive"))
      (node (ref "R39") (pin "1") (pinfunction "1_1") (pintype "passive"))
      (node (ref "R40") (pin "1") (pinfunction "1_1") (pintype "passive"))
      (node (ref "T5") (pin "1") (pinfunction "E_1") (pintype "passive"))
    )
    (net (code "84") (name "Net-(T6-E)") (class "Default")
      (node (ref "R41") (pin "1") (pinfunction "1_1") (pintype "passive"))
      (node (ref "R42") (pin "1") (pinfunction "1_1") (pintype "passive"))
      (node (ref "R43") (pin "1") (pinfunction "1_1") (pintype "passive"))
      (node (ref "R44") (pin "1") (pinfunction "1_1") (pintype "passive"))
      (node (ref "R45") (pin "1") (pinfunction "1_1") (pintype "passive"))
      (node (ref "R46") (pin "1") (pinfunction "1_1") (pintype "passive"))
      (node (ref "R47") (pin "1") (pinfunction "1_1") (pintype "passive"))
      (node (ref "R48") (pin "1") (pinfunction "1_1") (pintype "passive"))
      (node (ref "T6") (pin "1") (pinfunction "E_1") (pintype "passive"))
    )
    (net (code "85") (name "Net-(T7-E)") (class "Default")
      (node (ref "R49") (pin "1") (pinfunction "1_1") (pintype "passive"))
      (node (ref "R50") (pin "1") (pinfunction "1_1") (pintype "passive"))
      (node (ref "R51") (pin "1") (pinfunction "1_1") (pintype "passive"))
      (node (ref "R52") (pin "1") (pinfunction "1_1") (pintype "passive"))
      (node (ref "R53") (pin "1") (pinfunction "1_1") (pintype "passive"))
      (node (ref "R54") (pin "1") (pinfunction "1_1") (pintype "passive"))
      (node (ref "R55") (pin "1") (pinfunction "1_1") (pintype "passive"))
      (node (ref "R56") (pin "1") (pinfunction "1_1") (pintype "passive"))
      (node (ref "T7") (pin "1") (pinfunction "E_1") (pintype "passive"))
    )
    (net (code "86") (name "Net-(T8-E)") (class "Default")
      (node (ref "R57") (pin "1") (pinfunction "1_1") (pintype "passive"))
      (node (ref "R58") (pin "1") (pinfunction "1_1") (pintype "passive"))
      (node (ref "R59") (pin "1") (pinfunction "1_1") (pintype "passive"))
      (node (ref "R60") (pin "1") (pinfunction "1_1") (pintype "passive"))
      (node (ref "R61") (pin "1") (pinfunction "1_1") (pintype "passive"))
      (node (ref "R62") (pin "1") (pinfunction "1_1") (pintype "passive"))
      (node (ref "R63") (pin "1") (pinfunction "1_1") (pintype "passive"))
      (node (ref "R64") (pin "1") (pinfunction "1_1") (pintype "passive"))
      (node (ref "T8") (pin "1") (pinfunction "E_1") (pintype "passive"))
    )
    (net (code "87") (name "unconnected-(JP1-Pad1)") (class "Default")
      (node (ref "JP1") (pin "1") (pinfunction "1_1") (pintype "passive"))
    )
    (net (code "88") (name "unconnected-(JP1-Pad2)") (class "Default")
      (node (ref "JP1") (pin "2") (pinfunction "2_2") (pintype "passive"))
    )
    (net (code "89") (name "unconnected-(JP2-Pad7)") (class "Default")
      (node (ref "JP2") (pin "7") (pinfunction "7_7") (pintype "passive"))
    )
    (net (code "90") (name "unconnected-(JP2-Pad8)") (class "Default")
      (node (ref "JP2") (pin "8") (pinfunction "8_8") (pintype "passive"))
    )
    (net (code "91") (name "unconnected-(JP2-Pad9)") (class "Default")
      (node (ref "JP2") (pin "9") (pinfunction "9_9") (pintype "passive"))
    )
    (net (code "92") (name "unconnected-(JP2-Pad10)") (class "Default")
      (node (ref "JP2") (pin "10") (pinfunction "10_10") (pintype "passive"))
    )
    (net (code "93") (name "unconnected-(JP3-Pad1)") (class "Default")
      (node (ref "JP3") (pin "1") (pinfunction "1_1") (pintype "passive"))
    )
    (net (code "94") (name "unconnected-(JP3-Pad2)") (class "Default")
      (node (ref "JP3") (pin "2") (pinfunction "2_2") (pintype "passive"))
    )
    (net (code "95") (name "unconnected-(JP3-Pad3)") (class "Default")
      (node (ref "JP3") (pin "3") (pinfunction "3_3") (pintype "passive"))
    )
    (net (code "96") (name "unconnected-(JP3-Pad4)") (class "Default")
      (node (ref "JP3") (pin "4") (pinfunction "4_4") (pintype "passive"))
    )
    (net (code "97") (name "unconnected-(JP3-Pad6)") (class "Default")
      (node (ref "JP3") (pin "6") (pinfunction "6_6") (pintype "passive"))
    )
    (net (code "98") (name "unconnected-(JP3-Pad8)") (class "Default")
      (node (ref "JP3") (pin "8") (pinfunction "8_8") (pintype "passive"))
    )
    (net (code "99") (name "unconnected-(R32-Pad1)") (class "Default")
      (node (ref "R32") (pin "1") (pinfunction "1_1") (pintype "passive"))
    )
  )
)
